# 15-AM64x-04.net
KiCad netlist of a schematic drawn in Altium Designer
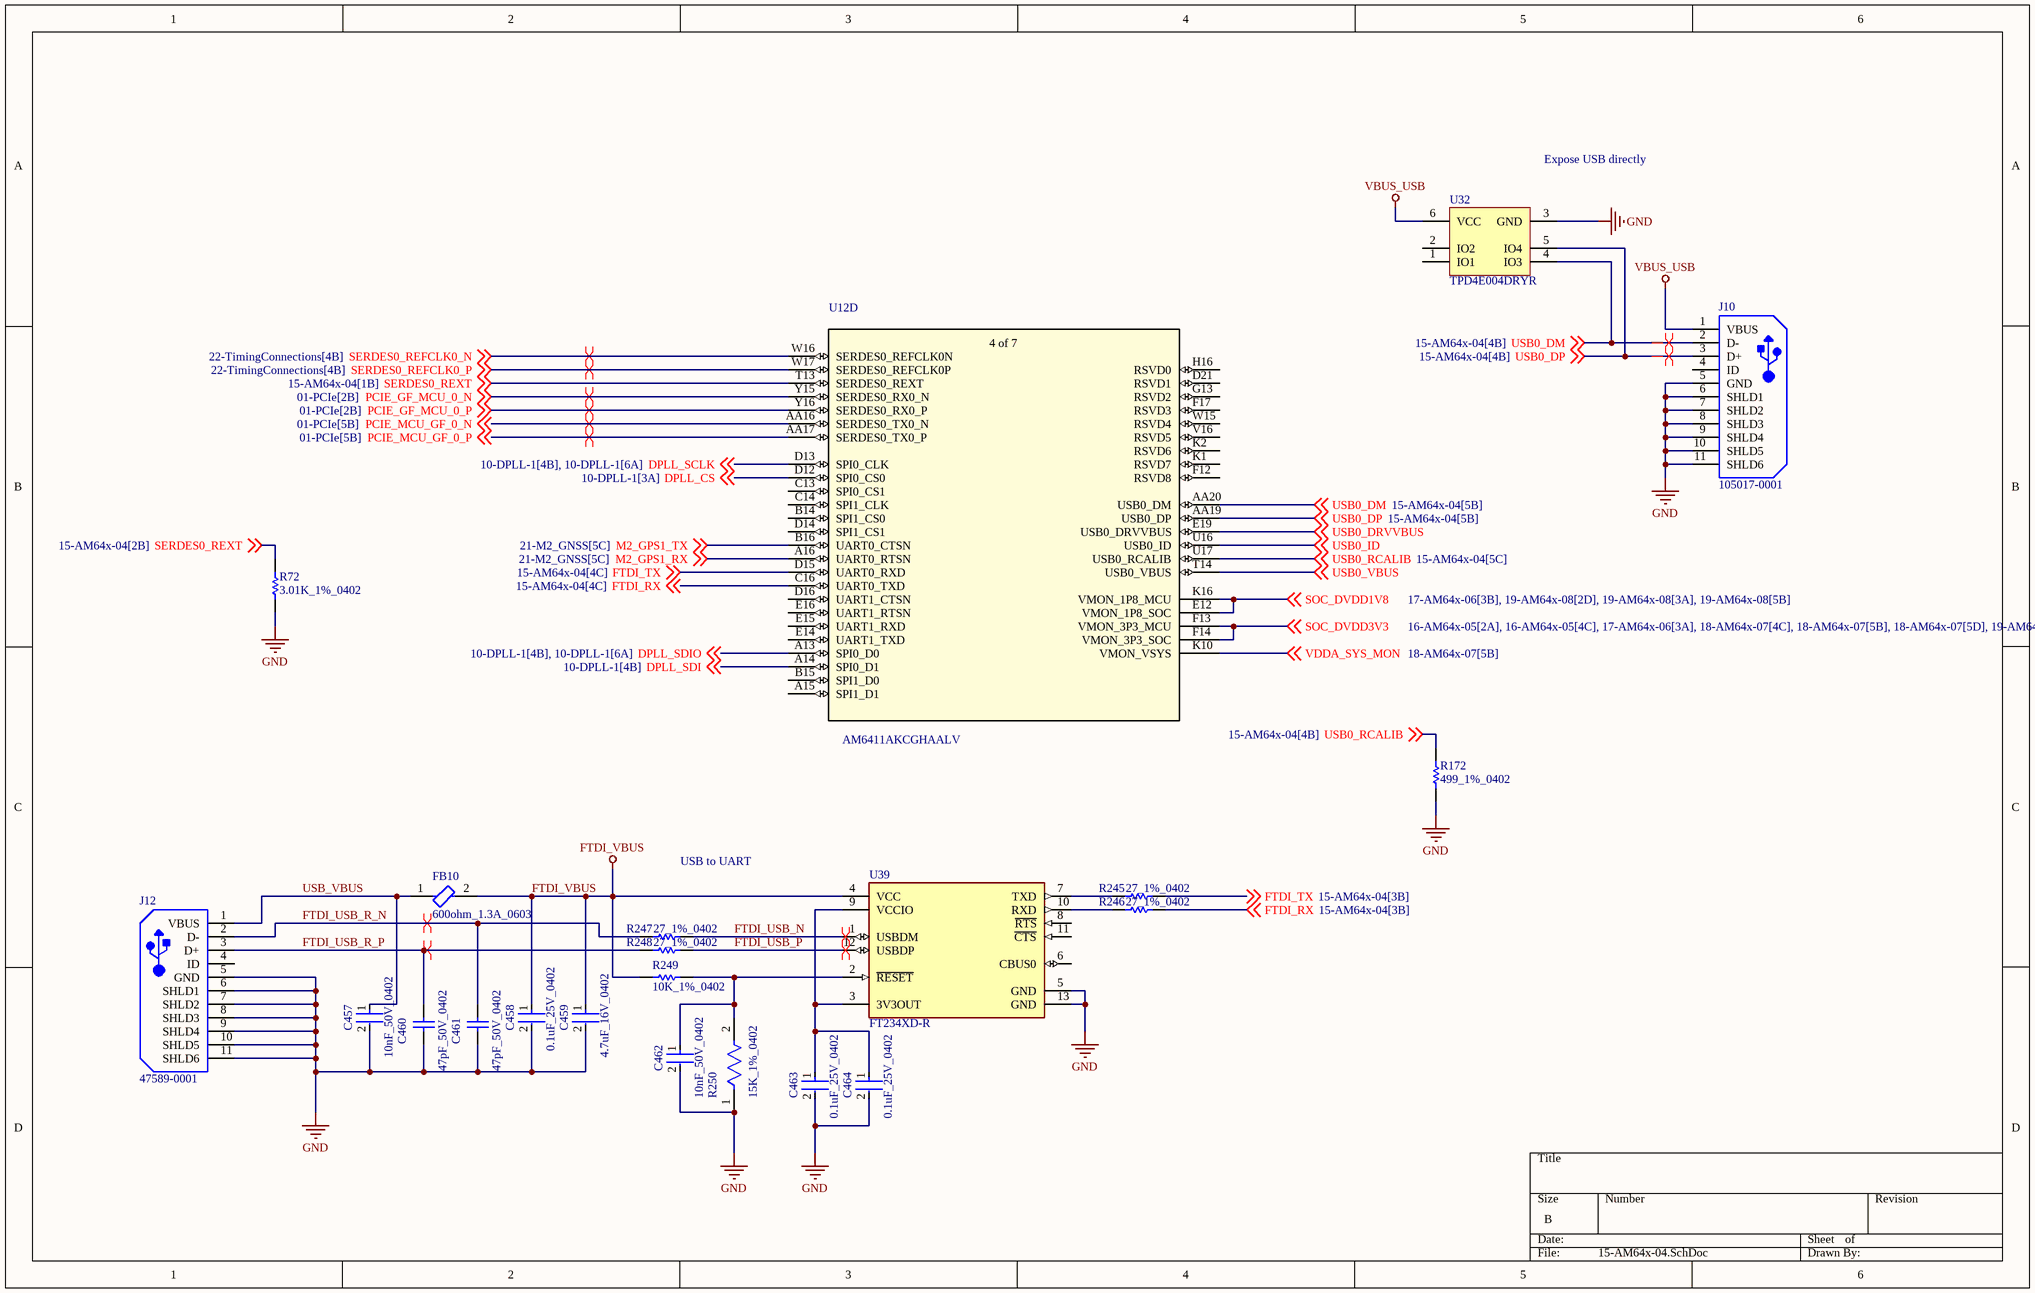
[diagram p0: 15-AM64x-04.SchDoc]

(export (version "E")
  (design (tool "Eeschema 10.0.6"))
  (components
    (comp (ref "C457")
      (value "10nF_50V_0402")
      (footprint "FP-CC0402-MFG")
      (description "CAP CER 10000PF 50V X7R 0402")
      (fields
        (field (name "OCTOPART") "https://octopart.com/cc0402krx7r9bb103-yageo-8376513")
        (field (name "MANUFACTURER PART NUMBER") "CC0402KRX7R9BB103")
      )
      (libsource (lib "Altium Content Vault") (part "11868f565c42a9108669ba33697ecf6"))
    )
    (comp (ref "C458")
      (value "0.1uF_25V_0402")
      (footprint "FP-0402-L_1_0_1-W_0_5_0_1-IPC_C")
      (description "General Purpose Ceramic Capacitor, 0402, 100nF, 10%, X7R, 15%, 25V")
      (fields (field (name "VOLTAGE") "25V") (field (name "TOLERANCE") "10%"))
      (libsource (lib "Altium Content Vault") (part "b4654b650e69147ec39a6b967a45e02"))
    )
    (comp (ref "C459")
      (value "4.7uF_16V_0402")
      (footprint "FP-CL829-IPC_C")
      (description "Cap Ceramic 4.7uF 16V X5R ±20% SMD 0402 +85°C Paper T/R")
      (fields (field (name "TOLERANCE") "20%"))
      (libsource (lib "Altium Content Vault") (part "b4654b650e69147ec39a6b967a45e02"))
    )
    (comp (ref "C460")
      (value "47pF_50V_0402")
      (footprint "CAPC1005X55X25LL05T10")
      (fields (field (name "PART NUMBER") "GRM1555C1H470JA01D") (field (name "MANUFACTURER") "Murata"))
      (libsource (lib "Altium Content Vault") (part "CAP"))
    )
    (comp (ref "C461")
      (value "47pF_50V_0402")
      (footprint "CAPC1005X55X25LL05T10")
      (fields (field (name "PART NUMBER") "GRM1555C1H470JA01D") (field (name "MANUFACTURER") "Murata"))
      (libsource (lib "Altium Content Vault") (part "CAP"))
    )
    (comp (ref "C462")
      (value "10nF_50V_0402")
      (footprint "FP-CC0402-MFG")
      (description "CAP CER 10000PF 50V X7R 0402")
      (fields
        (field (name "OCTOPART") "https://octopart.com/cc0402krx7r9bb103-yageo-8376513")
        (field (name "MANUFACTURER PART NUMBER") "CC0402KRX7R9BB103")
      )
      (libsource (lib "Altium Content Vault") (part "11868f565c42a9108669ba33697ecf6"))
    )
    (comp (ref "C463")
      (value "0.1uF_25V_0402")
      (footprint "FP-0402-L_1_0_1-W_0_5_0_1-IPC_C")
      (description "General Purpose Ceramic Capacitor, 0402, 100nF, 10%, X7R, 15%, 25V")
      (fields (field (name "VOLTAGE") "25V") (field (name "TOLERANCE") "10%"))
      (libsource (lib "Altium Content Vault") (part "b4654b650e69147ec39a6b967a45e02"))
    )
    (comp (ref "C464")
      (value "0.1uF_25V_0402")
      (footprint "FP-0402-L_1_0_1-W_0_5_0_1-IPC_C")
      (description "General Purpose Ceramic Capacitor, 0402, 100nF, 10%, X7R, 15%, 25V")
      (fields (field (name "VOLTAGE") "25V") (field (name "TOLERANCE") "10%"))
      (libsource (lib "Altium Content Vault") (part "b4654b650e69147ec39a6b967a45e02"))
    )
    (comp (ref "FB10")
      (value "600ohm_1.3A_0603")
      (footprint "FP-BLM18-0_15-t0_8-IPC_A")
      (description "Chip Ferrite Bead, 0603, 600Ω @ 100MHz, 0.15Ω, 25%, 1.3A")
      (fields (field (name "TOLERANCE") "25%"))
      (libsource (lib "Altium Content Vault") (part "5f30dd21d616792df468990f7003faa"))
    )
    (comp (ref "J10")
      (value "105017-0001")
      (footprint "USB-MICRO-B_V")
      (fields (field (name "MANUFACTURER") "Molex"))
      (libsource (lib "") (part "USB-5-6SHLD_1"))
    )
    (comp (ref "J12")
      (value "47589-0001")
      (footprint "MOLX-47589-0001_V")
      (description "Right Angle Female Type AB Micro USB Connector, 30 V, 1.8 A, -30 to 85 degC, RoHS, Tape and Reel")
      (fields (field (name "MANUFACTURER") "Molex"))
      (libsource (lib "Altium Content Vault") (part "USB-5-6SHLD"))
    )
    (comp (ref "R72")
      (value "3.01K_1%_0402")
      (footprint "RESC1005X40X25LL05T10")
      (fields (field (name "MANUFACTURER") "Yageo") (field (name "PART NUMBER") "RC0402FR-133K01L"))
      (libsource (lib "Altium Content Vault") (part "RES"))
    )
    (comp (ref "R172")
      (value "499_1%_0402")
      (footprint "RESC1005X40X25LL05T05")
      (fields (field (name "MANUFACTURER") "Vishay Dale") (field (name "PART NUMBER") "CRCW0402499RFKTD"))
      (libsource (lib "Altium Content Vault") (part "RES"))
    )
    (comp (ref "R245")
      (value "27_1%_0402")
      (footprint "RESC1005X40X25NL05T05")
      (fields (field (name "PART NUMBER") "CRCW040227R0FKED") (field (name "MANUFACTURER") "Vishay Dale"))
      (libsource (lib "Altium Content Vault") (part "RES"))
    )
    (comp (ref "R246")
      (value "27_1%_0402")
      (footprint "RESC1005X40X25NL05T05")
      (fields (field (name "PART NUMBER") "CRCW040227R0FKED") (field (name "MANUFACTURER") "Vishay Dale"))
      (libsource (lib "Altium Content Vault") (part "RES"))
    )
    (comp (ref "R247")
      (value "27_1%_0402")
      (footprint "RESC1005X40X25NL05T05")
      (fields (field (name "PART NUMBER") "CRCW040227R0FKED") (field (name "MANUFACTURER") "Vishay Dale"))
      (libsource (lib "Altium Content Vault") (part "RES"))
    )
    (comp (ref "R248")
      (value "27_1%_0402")
      (footprint "RESC1005X40X25NL05T05")
      (fields (field (name "PART NUMBER") "CRCW040227R0FKED") (field (name "MANUFACTURER") "Vishay Dale"))
      (libsource (lib "Altium Content Vault") (part "RES"))
    )
    (comp (ref "R249")
      (value "10K_1%_0402")
      (footprint "RESC1005X40X25LL05T10")
      (fields (field (name "PART NUMBER") "RC0402FR-0710KL") (field (name "MANUFACTURER") "Yageo / Phycomp"))
      (libsource (lib "Altium Content Vault") (part "RES"))
    )
    (comp (ref "R250")
      (value "15K_1%_0402")
      (footprint "FP-ERJ2R-MFG")
      (description "RES SMD 15K OHM 1% 1/10W 0402")
      (fields (field (name "TOLERANCE") "1%") (field (name "MANUFACTURER PART NUMBER") "ERJ-2RKF1502X"))
      (libsource (lib "Altium Content Vault") (part "1029c3af85768c4190bb7ad29bc67b5"))
    )
    (comp (ref "U12")
      (value "AM6411AKCGHAALV")
      (footprint "FCBGA441_ALV_TEX")
      (description "No Description Available")
      (libsource (lib "AM6411AKCGHAALV") (part "AM6411AKCGHAALV"))
    )
    (comp (ref "U32")
      (value "TPD4E004DRYR")
      (footprint "DRY0006A")
      (fields (field (name "MANUFACTURER") "Texas Instruments"))
      (libsource (lib "Altium Content Vault") (part "TI-TPD4E004-SON_DRY-6"))
    )
    (comp (ref "U39")
      (value "FT234XD-R")
      (footprint "FP-DFN-12-IPC_B")
      (description "IC USB SERIAL BASIC UART 12DFN")
      (libsource (lib "Altium Content Vault") (part "4bef3367ed9f9051bcb84ab46edda1c"))
    )
  )
  (nets
    (net (code "1") (name "/FTDI_USB_N") (class "Default")
      (node (ref "R247") (pin "2") (pinfunction "2_2") (pintype "passive"))
      (node (ref "U39") (pin "1") (pinfunction "USBDM_1") (pintype "bidirectional"))
    )
    (net (code "2") (name "/FTDI_USB_P") (class "Default")
      (node (ref "R248") (pin "2") (pinfunction "2_2") (pintype "passive"))
      (node (ref "U39") (pin "12") (pinfunction "USBDP_12") (pintype "bidirectional"))
    )
    (net (code "3") (name "/FTDI_USB_R_N") (class "Default")
      (node (ref "C461") (pin "2") (pinfunction "2_2") (pintype "passive"))
      (node (ref "J12") (pin "2") (pinfunction "D-_2") (pintype "passive"))
      (node (ref "R247") (pin "1") (pinfunction "1_1") (pintype "passive"))
    )
    (net (code "4") (name "/FTDI_USB_R_P") (class "Default")
      (node (ref "C460") (pin "2") (pinfunction "2_2") (pintype "passive"))
      (node (ref "J12") (pin "3") (pinfunction "D+_3") (pintype "passive"))
      (node (ref "R248") (pin "1") (pinfunction "1_1") (pintype "passive"))
    )
    (net (code "5") (name "/USB_VBUS") (class "Default")
      (node (ref "C457") (pin "1") (pinfunction "1_1") (pintype "passive"))
      (node (ref "FB10") (pin "1") (pinfunction "1_1") (pintype "passive"))
      (node (ref "J12") (pin "1") (pinfunction "VBUS_1") (pintype "passive"))
    )
    (net (code "6") (name "DPLL_CS") (class "Default")
      (node (ref "U12") (pin "D12") (pinfunction "SPI0_CS0_D12") (pintype "bidirectional"))
    )
    (net (code "7") (name "DPLL_SCLK") (class "Default")
      (node (ref "U12") (pin "D13") (pinfunction "SPI0_CLK_D13") (pintype "bidirectional"))
    )
    (net (code "8") (name "DPLL_SDI") (class "Default")
      (node (ref "U12") (pin "A14") (pinfunction "SPI0_D1_A14") (pintype "bidirectional"))
    )
    (net (code "9") (name "DPLL_SDIO") (class "Default")
      (node (ref "U12") (pin "A13") (pinfunction "SPI0_D0_A13") (pintype "bidirectional"))
    )
    (net (code "10") (name "FTDI_RX") (class "Default")
      (node (ref "R246") (pin "2") (pinfunction "2_2") (pintype "passive"))
      (node (ref "U12") (pin "C16") (pinfunction "UART0_TXD_C16") (pintype "bidirectional"))
    )
    (net (code "11") (name "FTDI_TX") (class "Default")
      (node (ref "R245") (pin "2") (pinfunction "2_2") (pintype "passive"))
      (node (ref "U12") (pin "D15") (pinfunction "UART0_RXD_D15") (pintype "bidirectional"))
    )
    (net (code "12") (name "FTDI_VBUS") (class "Default")
      (node (ref "C458") (pin "1") (pinfunction "1_1") (pintype "passive"))
      (node (ref "C459") (pin "1") (pinfunction "1_1") (pintype "passive"))
      (node (ref "FB10") (pin "2") (pinfunction "2_2") (pintype "passive"))
      (node (ref "R249") (pin "2") (pinfunction "2_2") (pintype "passive"))
      (node (ref "U39") (pin "4") (pinfunction "VCC_4") (pintype "power_in"))
    )
    (net (code "13") (name "GND") (class "Default")
      (node (ref "C457") (pin "2") (pinfunction "2_2") (pintype "passive"))
      (node (ref "C458") (pin "2") (pinfunction "2_2") (pintype "passive"))
      (node (ref "C459") (pin "2") (pinfunction "2_2") (pintype "passive"))
      (node (ref "C460") (pin "1") (pinfunction "1_1") (pintype "passive"))
      (node (ref "C461") (pin "1") (pinfunction "1_1") (pintype "passive"))
      (node (ref "C462") (pin "2") (pinfunction "2_2") (pintype "passive"))
      (node (ref "C463") (pin "2") (pinfunction "2_2") (pintype "passive"))
      (node (ref "C464") (pin "2") (pinfunction "2_2") (pintype "passive"))
      (node (ref "J10") (pin "10") (pinfunction "SHLD5_10") (pintype "passive"))
      (node (ref "J10") (pin "11") (pinfunction "SHLD6_11") (pintype "passive"))
      (node (ref "J10") (pin "5") (pinfunction "GND_5") (pintype "passive"))
      (node (ref "J10") (pin "6") (pinfunction "SHLD1_6") (pintype "passive"))
      (node (ref "J10") (pin "7") (pinfunction "SHLD2_7") (pintype "passive"))
      (node (ref "J10") (pin "8") (pinfunction "SHLD3_8") (pintype "passive"))
      (node (ref "J10") (pin "9") (pinfunction "SHLD4_9") (pintype "passive"))
      (node (ref "J12") (pin "10") (pinfunction "SHLD5_10") (pintype "passive"))
      (node (ref "J12") (pin "11") (pinfunction "SHLD6_11") (pintype "passive"))
      (node (ref "J12") (pin "5") (pinfunction "GND_5") (pintype "passive"))
      (node (ref "J12") (pin "6") (pinfunction "SHLD1_6") (pintype "passive"))
      (node (ref "J12") (pin "7") (pinfunction "SHLD2_7") (pintype "passive"))
      (node (ref "J12") (pin "8") (pinfunction "SHLD3_8") (pintype "passive"))
      (node (ref "J12") (pin "9") (pinfunction "SHLD4_9") (pintype "passive"))
      (node (ref "R172") (pin "1") (pinfunction "1_1") (pintype "passive"))
      (node (ref "R250") (pin "1") (pinfunction "1_1") (pintype "passive"))
      (node (ref "R72") (pin "1") (pinfunction "1_1") (pintype "passive"))
      (node (ref "U32") (pin "3") (pinfunction "GND_3") (pintype "power_in"))
      (node (ref "U39") (pin "13") (pinfunction "GND_13") (pintype "power_in"))
      (node (ref "U39") (pin "5") (pinfunction "GND_5") (pintype "power_in"))
    )
    (net (code "14") (name "M2_GPS1_RX") (class "Default")
      (node (ref "U12") (pin "A16") (pinfunction "UART0_RTSN_A16") (pintype "bidirectional"))
    )
    (net (code "15") (name "M2_GPS1_TX") (class "Default")
      (node (ref "U12") (pin "B16") (pinfunction "UART0_CTSN_B16") (pintype "bidirectional"))
    )
    (net (code "16") (name "Net-(U39-3V3OUT)") (class "Default")
      (node (ref "C463") (pin "1") (pinfunction "1_1") (pintype "passive"))
      (node (ref "C464") (pin "1") (pinfunction "1_1") (pintype "passive"))
      (node (ref "U39") (pin "3") (pinfunction "3V3OUT_3") (pintype "power_in"))
      (node (ref "U39") (pin "9") (pinfunction "VCCIO_9") (pintype "power_in"))
    )
    (net (code "17") (name "Net-(U39-RXD)") (class "Default")
      (node (ref "R246") (pin "1") (pinfunction "1_1") (pintype "passive"))
      (node (ref "U39") (pin "10") (pinfunction "RXD_10") (pintype "output"))
    )
    (net (code "18") (name "Net-(U39-TXD)") (class "Default")
      (node (ref "R245") (pin "1") (pinfunction "1_1") (pintype "passive"))
      (node (ref "U39") (pin "7") (pinfunction "TXD_7") (pintype "output"))
    )
    (net (code "19") (name "Net-(U39-~{RESET})") (class "Default")
      (node (ref "C462") (pin "1") (pinfunction "1_1") (pintype "passive"))
      (node (ref "R249") (pin "1") (pinfunction "1_1") (pintype "passive"))
      (node (ref "R250") (pin "2") (pinfunction "2_2") (pintype "passive"))
      (node (ref "U39") (pin "2") (pinfunction "~{RESET}_2") (pintype "input"))
    )
    (net (code "20") (name "PCIE_GF_MCU_0_N") (class "Default")
      (node (ref "U12") (pin "Y15") (pinfunction "SERDES0_RX0_N_Y15") (pintype "bidirectional"))
    )
    (net (code "21") (name "PCIE_GF_MCU_0_P") (class "Default")
      (node (ref "U12") (pin "Y16") (pinfunction "SERDES0_RX0_P_Y16") (pintype "bidirectional"))
    )
    (net (code "22") (name "PCIE_MCU_GF_0_N") (class "Default")
      (node (ref "U12") (pin "AA16") (pinfunction "SERDES0_TX0_N_AA16") (pintype "bidirectional"))
    )
    (net (code "23") (name "PCIE_MCU_GF_0_P") (class "Default")
      (node (ref "U12") (pin "AA17") (pinfunction "SERDES0_TX0_P_AA17") (pintype "bidirectional"))
    )
    (net (code "24") (name "SERDES0_REFCLK0_N") (class "Default")
      (node (ref "U12") (pin "W16") (pinfunction "SERDES0_REFCLK0N_W16") (pintype "bidirectional"))
    )
    (net (code "25") (name "SERDES0_REFCLK0_P") (class "Default")
      (node (ref "U12") (pin "W17") (pinfunction "SERDES0_REFCLK0P_W17") (pintype "bidirectional"))
    )
    (net (code "26") (name "SERDES0_REXT") (class "Default")
      (node (ref "R72") (pin "2") (pinfunction "2_2") (pintype "passive"))
      (node (ref "U12") (pin "T13") (pinfunction "SERDES0_REXT_T13") (pintype "bidirectional"))
    )
    (net (code "27") (name "SOC_DVDD1V8") (class "Default")
      (node (ref "U12") (pin "E12") (pinfunction "VMON_1P8_SOC_E12") (pintype "passive"))
      (node (ref "U12") (pin "K16") (pinfunction "VMON_1P8_MCU_K16") (pintype "passive"))
    )
    (net (code "28") (name "SOC_DVDD3V3") (class "Default")
      (node (ref "U12") (pin "F13") (pinfunction "VMON_3P3_MCU_F13") (pintype "passive"))
      (node (ref "U12") (pin "F14") (pinfunction "VMON_3P3_SOC_F14") (pintype "passive"))
    )
    (net (code "29") (name "USB0_DM") (class "Default")
      (node (ref "J10") (pin "2") (pinfunction "D-_2") (pintype "passive"))
      (node (ref "U12") (pin "AA20") (pinfunction "USB0_DM_AA20") (pintype "bidirectional"))
      (node (ref "U32") (pin "4") (pinfunction "IO3_4") (pintype "passive"))
    )
    (net (code "30") (name "USB0_DP") (class "Default")
      (node (ref "J10") (pin "3") (pinfunction "D+_3") (pintype "passive"))
      (node (ref "U12") (pin "AA19") (pinfunction "USB0_DP_AA19") (pintype "bidirectional"))
      (node (ref "U32") (pin "5") (pinfunction "IO4_5") (pintype "passive"))
    )
    (net (code "31") (name "USB0_DRVVBUS") (class "Default")
      (node (ref "U12") (pin "E19") (pinfunction "USB0_DRVVBUS_E19") (pintype "bidirectional"))
    )
    (net (code "32") (name "USB0_ID") (class "Default")
      (node (ref "U12") (pin "U16") (pinfunction "USB0_ID_U16") (pintype "bidirectional"))
    )
    (net (code "33") (name "USB0_RCALIB") (class "Default")
      (node (ref "R172") (pin "2") (pinfunction "2_2") (pintype "passive"))
      (node (ref "U12") (pin "U17") (pinfunction "USB0_RCALIB_U17") (pintype "bidirectional"))
    )
    (net (code "34") (name "USB0_VBUS") (class "Default")
      (node (ref "U12") (pin "T14") (pinfunction "USB0_VBUS_T14") (pintype "bidirectional"))
    )
    (net (code "35") (name "VBUS_USB") (class "Default")
      (node (ref "J10") (pin "1") (pinfunction "VBUS_1") (pintype "passive"))
      (node (ref "U32") (pin "6") (pinfunction "VCC_6") (pintype "power_in"))
    )
    (net (code "36") (name "VDDA_SYS_MON") (class "Default")
      (node (ref "U12") (pin "K10") (pinfunction "VMON_VSYS_K10") (pintype "passive"))
    )
    (net (code "37") (name "unconnected-(J10-ID-Pad4)") (class "Default")
      (node (ref "J10") (pin "4") (pinfunction "ID_4") (pintype "passive"))
    )
    (net (code "38") (name "unconnected-(J12-ID-Pad4)") (class "Default")
      (node (ref "J12") (pin "4") (pinfunction "ID_4") (pintype "passive"))
    )
    (net (code "39") (name "unconnected-(U12D-RSVD0-PadH16)") (class "Default")
      (node (ref "U12") (pin "H16") (pinfunction "RSVD0_H16") (pintype "bidirectional"))
    )
    (net (code "40") (name "unconnected-(U12D-RSVD1-PadD21)") (class "Default")
      (node (ref "U12") (pin "D21") (pinfunction "RSVD1_D21") (pintype "bidirectional"))
    )
    (net (code "41") (name "unconnected-(U12D-RSVD2-PadG13)") (class "Default")
      (node (ref "U12") (pin "G13") (pinfunction "RSVD2_G13") (pintype "bidirectional"))
    )
    (net (code "42") (name "unconnected-(U12D-RSVD3-PadF17)") (class "Default")
      (node (ref "U12") (pin "F17") (pinfunction "RSVD3_F17") (pintype "bidirectional"))
    )
    (net (code "43") (name "unconnected-(U12D-RSVD4-PadW15)") (class "Default")
      (node (ref "U12") (pin "W15") (pinfunction "RSVD4_W15") (pintype "bidirectional"))
    )
    (net (code "44") (name "unconnected-(U12D-RSVD5-PadV16)") (class "Default")
      (node (ref "U12") (pin "V16") (pinfunction "RSVD5_V16") (pintype "bidirectional"))
    )
    (net (code "45") (name "unconnected-(U12D-RSVD6-PadK2)") (class "Default")
      (node (ref "U12") (pin "K2") (pinfunction "RSVD6_K2") (pintype "bidirectional"))
    )
    (net (code "46") (name "unconnected-(U12D-RSVD7-PadK1)") (class "Default")
      (node (ref "U12") (pin "K1") (pinfunction "RSVD7_K1") (pintype "bidirectional"))
    )
    (net (code "47") (name "unconnected-(U12D-RSVD8-PadF12)") (class "Default")
      (node (ref "U12") (pin "F12") (pinfunction "RSVD8_F12") (pintype "bidirectional"))
    )
    (net (code "48") (name "unconnected-(U12D-SPI0_CS1-PadC13)") (class "Default")
      (node (ref "U12") (pin "C13") (pinfunction "SPI0_CS1_C13") (pintype "bidirectional"))
    )
    (net (code "49") (name "unconnected-(U12D-SPI1_CLK-PadC14)") (class "Default")
      (node (ref "U12") (pin "C14") (pinfunction "SPI1_CLK_C14") (pintype "bidirectional"))
    )
    (net (code "50") (name "unconnected-(U12D-SPI1_CS0-PadB14)") (class "Default")
      (node (ref "U12") (pin "B14") (pinfunction "SPI1_CS0_B14") (pintype "bidirectional"))
    )
    (net (code "51") (name "unconnected-(U12D-SPI1_CS1-PadD14)") (class "Default")
      (node (ref "U12") (pin "D14") (pinfunction "SPI1_CS1_D14") (pintype "bidirectional"))
    )
    (net (code "52") (name "unconnected-(U12D-SPI1_D0-PadB15)") (class "Default")
      (node (ref "U12") (pin "B15") (pinfunction "SPI1_D0_B15") (pintype "bidirectional"))
    )
    (net (code "53") (name "unconnected-(U12D-SPI1_D1-PadA15)") (class "Default")
      (node (ref "U12") (pin "A15") (pinfunction "SPI1_D1_A15") (pintype "bidirectional"))
    )
    (net (code "54") (name "unconnected-(U12D-UART1_CTSN-PadD16)") (class "Default")
      (node (ref "U12") (pin "D16") (pinfunction "UART1_CTSN_D16") (pintype "bidirectional"))
    )
    (net (code "55") (name "unconnected-(U12D-UART1_RTSN-PadE16)") (class "Default")
      (node (ref "U12") (pin "E16") (pinfunction "UART1_RTSN_E16") (pintype "bidirectional"))
    )
    (net (code "56") (name "unconnected-(U12D-UART1_RXD-PadE15)") (class "Default")
      (node (ref "U12") (pin "E15") (pinfunction "UART1_RXD_E15") (pintype "bidirectional"))
    )
    (net (code "57") (name "unconnected-(U12D-UART1_TXD-PadE14)") (class "Default")
      (node (ref "U12") (pin "E14") (pinfunction "UART1_TXD_E14") (pintype "bidirectional"))
    )
    (net (code "58") (name "unconnected-(U32-IO1-Pad1)") (class "Default")
      (node (ref "U32") (pin "1") (pinfunction "IO1_1") (pintype "passive"))
    )
    (net (code "59") (name "unconnected-(U32-IO2-Pad2)") (class "Default")
      (node (ref "U32") (pin "2") (pinfunction "IO2_2") (pintype "passive"))
    )
    (net (code "60") (name "unconnected-(U39-CBUS0-Pad6)") (class "Default")
      (node (ref "U39") (pin "6") (pinfunction "CBUS0_6") (pintype "bidirectional"))
    )
    (net (code "61") (name "unconnected-(U39-~{CTS}-Pad11)") (class "Default")
      (node (ref "U39") (pin "11") (pinfunction "~{CTS}_11") (pintype "input"))
    )
    (net (code "62") (name "unconnected-(U39-~{RTS}-Pad8)") (class "Default")
      (node (ref "U39") (pin "8") (pinfunction "~{RTS}_8") (pintype "input"))
    )
  )
)
